# MA_board_2.net
KiCad netlist of a schematic drawn in EAGLE
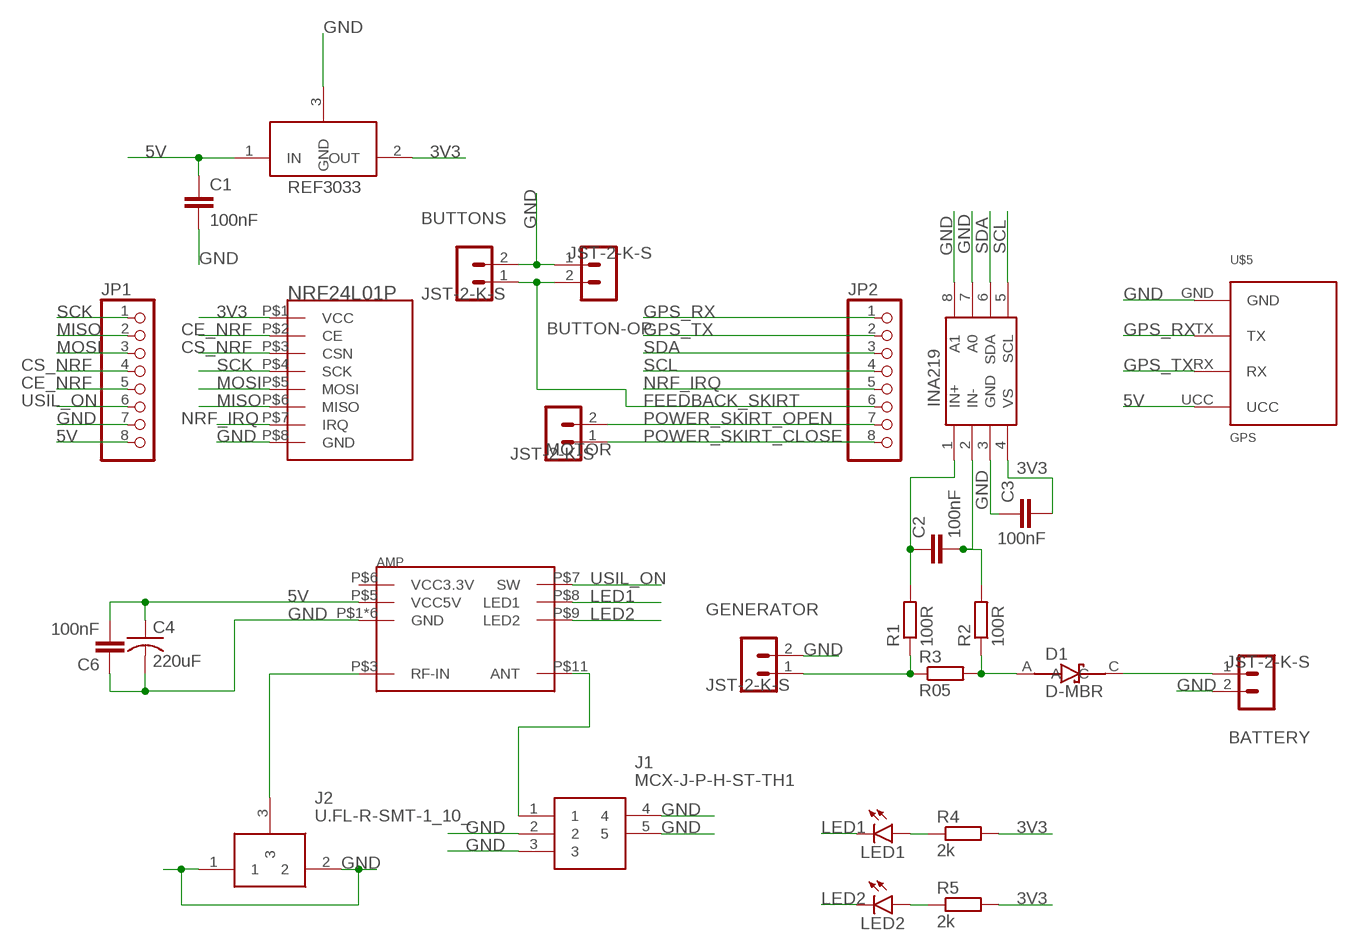
[diagram p0: schematic, sheet 1]

(export (version "E")
  (design (tool "Eeschema 10.0.6"))
  (components
    (comp (ref "AMP")
      (value "XQ-02A")
      (footprint "eagle-import:XQ-02A")
      (libsource (lib "eagle-import") (part "XQ-02A"))
    )
    (comp (ref "BATTERY")
      (value "JST-2-K-S")
      (footprint "eagle-import:B2B-PH-K-S")
      (libsource (lib "eagle-import") (part "JST-2-K-S"))
    )
    (comp (ref "BUTTON-OP")
      (value "JST-2-K-S")
      (footprint "eagle-import:B2B-PH-K-S")
      (libsource (lib "eagle-import") (part "JST-2-K-S"))
    )
    (comp (ref "BUTTONS")
      (value "JST-2-K-S")
      (footprint "eagle-import:B2B-PH-K-S")
      (libsource (lib "eagle-import") (part "JST-2-K-S"))
    )
    (comp (ref "C1")
      (value "100nF")
      (footprint "eagle-import:C0603")
      (libsource (lib "eagle-import") (part "C-EUC0603"))
    )
    (comp (ref "C2")
      (value "100nF")
      (footprint "eagle-import:C0603")
      (libsource (lib "eagle-import") (part "C-EUC0603"))
    )
    (comp (ref "C3")
      (value "100nF")
      (footprint "eagle-import:C0603")
      (libsource (lib "eagle-import") (part "C-EUC0603"))
    )
    (comp (ref "C4")
      (value "220uF")
      (footprint "eagle-import:ECAP220-CMD")
      (libsource (lib "eagle-import") (part "ECAPECAP220"))
    )
    (comp (ref "C6")
      (value "100nF")
      (footprint "eagle-import:C0603")
      (libsource (lib "eagle-import") (part "C-EUC0603"))
    )
    (comp (ref "D1")
      (value "D-MBR")
      (footprint "eagle-import:SOD123")
      (fields (field (name "MF") "ON Semiconductor") (field (name "MP") "MBR0520LT1G"))
      (libsource (lib "eagle-import") (part "DIODE-MBR"))
    )
    (comp (ref "GENERATOR")
      (value "JST-2-K-S")
      (footprint "eagle-import:B2B-PH-K-S")
      (libsource (lib "eagle-import") (part "JST-2-K-S"))
    )
    (comp (ref "INA219")
      (value "INA219AID")
      (footprint "eagle-import:SOT23-8")
      (libsource (lib "eagle-import") (part "INA219AID"))
    )
    (comp (ref "J1")
      (value "MCX-J-P-H-ST-TH1")
      (footprint "eagle-import:MCXJPHSTTH1")
      (fields (field (name "MOUSER_PART_NUMBER") "200-MCXJPHSTTH1"))
      (libsource (lib "eagle-import") (part "MCX-J-P-H-ST-TH1"))
    )
    (comp (ref "J2")
      (value "U.FL-R-SMT-1_10_")
      (footprint "eagle-import:U.FL-R-SMT-1(10)")
      (fields
        (field (name "ARROW_PART_NUMBER") "U.FL-R-SMT-1(10)")
        (field (name "MOUSER_PART_NUMBER") "798-U.FL-R-SMT-110")
      )
      (libsource (lib "eagle-import") (part "U.FL-R-SMT-1_10_"))
    )
    (comp (ref "JP1")
      (value "PINHD-1X8-SHORT-PAD")
      (footprint "eagle-import:1X08")
      (libsource (lib "eagle-import") (part "PINHD-1X8-SHORT-PAD"))
    )
    (comp (ref "JP2")
      (value "PINHD-1X8-SHORT-PAD")
      (footprint "eagle-import:1X08")
      (libsource (lib "eagle-import") (part "PINHD-1X8-SHORT-PAD"))
    )
    (comp (ref "LED1")
      (value "LEDSML0603")
      (footprint "eagle-import:SML0603")
      (libsource (lib "eagle-import") (part "LEDSML0603"))
    )
    (comp (ref "LED2")
      (value "LEDSML0603")
      (footprint "eagle-import:SML0603")
      (libsource (lib "eagle-import") (part "LEDSML0603"))
    )
    (comp (ref "MOTOR")
      (value "JST-2-K-S")
      (footprint "eagle-import:B2B-PH-K-S")
      (libsource (lib "eagle-import") (part "JST-2-K-S"))
    )
    (comp (ref "NRF24L01P")
      (value "NRF24L01_ML01SP4")
      (footprint "eagle-import:NRF24L01_ML01SP4")
      (libsource (lib "eagle-import") (part "NRF24L01_ML01SP4"))
    )
    (comp (ref "R1")
      (value "100R")
      (footprint "eagle-import:R0603")
      (libsource (lib "eagle-import") (part "R-EU_R0603"))
    )
    (comp (ref "R2")
      (value "100R")
      (footprint "eagle-import:R0603")
      (libsource (lib "eagle-import") (part "R-EU_R0603"))
    )
    (comp (ref "R3")
      (value "R05")
      (footprint "eagle-import:R2512")
      (libsource (lib "eagle-import") (part "R-EU_R2512"))
    )
    (comp (ref "R4")
      (value "2k")
      (footprint "eagle-import:R0603")
      (libsource (lib "eagle-import") (part "R-EU_R0603"))
    )
    (comp (ref "R5")
      (value "2k")
      (footprint "eagle-import:R0603")
      (libsource (lib "eagle-import") (part "R-EU_R0603"))
    )
    (comp (ref "REF3033")
      (value "REF3033")
      (footprint "eagle-import:SOT23-3")
      (libsource (lib "eagle-import") (part "REF3033"))
    )
    (comp (ref "U$5")
      (value "GPS")
      (footprint "eagle-import:GPS")
      (libsource (lib "eagle-import") (part "GPS"))
    )
  )
  (nets
    (net (code "1") (name "/3V3") (class "Default")
      (node (ref "C3") (pin "2") (pinfunction "2_2") (pintype "passive"))
      (node (ref "INA219") (pin "4") (pinfunction "VS_4") (pintype "bidirectional"))
      (node (ref "NRF24L01P") (pin "P$1") (pinfunction "VCC_P$1") (pintype "bidirectional"))
      (node (ref "R4") (pin "2") (pinfunction "2_2") (pintype "passive"))
      (node (ref "R5") (pin "2") (pinfunction "2_2") (pintype "passive"))
      (node (ref "REF3033") (pin "2") (pinfunction "OUT_2") (pintype "output"))
    )
    (net (code "2") (name "/5V") (class "Default")
      (node (ref "AMP") (pin "P$5") (pinfunction "VCC5V_P$5") (pintype "bidirectional"))
      (node (ref "C1") (pin "1") (pinfunction "1_1") (pintype "passive"))
      (node (ref "C4") (pin "P$1") (pinfunction "1_P$1") (pintype "passive"))
      (node (ref "C6") (pin "2") (pinfunction "2_2") (pintype "passive"))
      (node (ref "JP1") (pin "8") (pinfunction "8_8") (pintype "passive"))
      (node (ref "REF3033") (pin "1") (pinfunction "IN_1") (pintype "input"))
      (node (ref "U$5") (pin "UCC") (pinfunction "UCC_UCC") (pintype "bidirectional"))
    )
    (net (code "3") (name "/CE_NRF") (class "Default")
      (node (ref "JP1") (pin "5") (pinfunction "5_5") (pintype "passive"))
      (node (ref "NRF24L01P") (pin "P$2") (pinfunction "CE_P$2") (pintype "bidirectional"))
    )
    (net (code "4") (name "/CS_NRF") (class "Default")
      (node (ref "JP1") (pin "4") (pinfunction "4_4") (pintype "passive"))
      (node (ref "NRF24L01P") (pin "P$3") (pinfunction "CSN_P$3") (pintype "bidirectional"))
    )
    (net (code "5") (name "/FEEDBACK_SKIRT") (class "Default")
      (node (ref "BUTTON-OP") (pin "2") (pinfunction "2_2") (pintype "passive"))
      (node (ref "BUTTONS") (pin "1") (pinfunction "1_1") (pintype "passive"))
      (node (ref "JP2") (pin "6") (pinfunction "6_6") (pintype "passive"))
    )
    (net (code "6") (name "/GND") (class "Default")
      (node (ref "AMP") (pin "P$1") (pinfunction "GND_P$1") (pintype "bidirectional"))
      (node (ref "AMP") (pin "P$10") (pinfunction "GND_P$10") (pintype "bidirectional"))
      (node (ref "AMP") (pin "P$12") (pinfunction "GND_P$12") (pintype "bidirectional"))
      (node (ref "AMP") (pin "P$13") (pinfunction "GND_P$13") (pintype "bidirectional"))
      (node (ref "AMP") (pin "P$2") (pinfunction "GND_P$2") (pintype "bidirectional"))
      (node (ref "AMP") (pin "P$4") (pinfunction "GND_P$4") (pintype "bidirectional"))
      (node (ref "BATTERY") (pin "2") (pinfunction "2_2") (pintype "passive"))
      (node (ref "BUTTON-OP") (pin "1") (pinfunction "1_1") (pintype "passive"))
      (node (ref "BUTTONS") (pin "2") (pinfunction "2_2") (pintype "passive"))
      (node (ref "C1") (pin "2") (pinfunction "2_2") (pintype "passive"))
      (node (ref "C3") (pin "1") (pinfunction "1_1") (pintype "passive"))
      (node (ref "C4") (pin "P$2") (pinfunction "2_P$2") (pintype "passive"))
      (node (ref "C6") (pin "1") (pinfunction "1_1") (pintype "passive"))
      (node (ref "GENERATOR") (pin "2") (pinfunction "2_2") (pintype "passive"))
      (node (ref "INA219") (pin "3") (pinfunction "GND_3") (pintype "bidirectional"))
      (node (ref "INA219") (pin "7") (pinfunction "A0_7") (pintype "bidirectional"))
      (node (ref "INA219") (pin "8") (pinfunction "A1_8") (pintype "bidirectional"))
      (node (ref "J1") (pin "2") (pinfunction "2_2") (pintype "bidirectional"))
      (node (ref "J1") (pin "3") (pinfunction "3_3") (pintype "bidirectional"))
      (node (ref "J1") (pin "4") (pinfunction "4_4") (pintype "bidirectional"))
      (node (ref "J1") (pin "5") (pinfunction "5_5") (pintype "bidirectional"))
      (node (ref "J2") (pin "1") (pinfunction "1_1") (pintype "bidirectional"))
      (node (ref "J2") (pin "2") (pinfunction "2_2") (pintype "bidirectional"))
      (node (ref "JP1") (pin "7") (pinfunction "7_7") (pintype "passive"))
      (node (ref "NRF24L01P") (pin "P$8") (pinfunction "GND_P$8") (pintype "bidirectional"))
      (node (ref "REF3033") (pin "3") (pinfunction "GND_3") (pintype "power_in"))
      (node (ref "U$5") (pin "GND") (pinfunction "GND_GND") (pintype "bidirectional"))
    )
    (net (code "7") (name "/GPS_RX") (class "Default")
      (node (ref "JP2") (pin "1") (pinfunction "1_1") (pintype "passive"))
      (node (ref "U$5") (pin "TX") (pinfunction "TX_TX") (pintype "bidirectional"))
    )
    (net (code "8") (name "/GPS_TX") (class "Default")
      (node (ref "JP2") (pin "2") (pinfunction "2_2") (pintype "passive"))
      (node (ref "U$5") (pin "RX") (pinfunction "RX_RX") (pintype "bidirectional"))
    )
    (net (code "9") (name "/LED1") (class "Default")
      (node (ref "AMP") (pin "P$8") (pinfunction "LED1_P$8") (pintype "bidirectional"))
      (node (ref "LED1") (pin "C") (pinfunction "C_C") (pintype "passive"))
    )
    (net (code "10") (name "/LED2") (class "Default")
      (node (ref "AMP") (pin "P$9") (pinfunction "LED2_P$9") (pintype "bidirectional"))
      (node (ref "LED2") (pin "C") (pinfunction "C_C") (pintype "passive"))
    )
    (net (code "11") (name "/MISO") (class "Default")
      (node (ref "JP1") (pin "2") (pinfunction "2_2") (pintype "passive"))
      (node (ref "NRF24L01P") (pin "P$6") (pinfunction "MISO_P$6") (pintype "bidirectional"))
    )
    (net (code "12") (name "/MOSI") (class "Default")
      (node (ref "JP1") (pin "3") (pinfunction "3_3") (pintype "passive"))
      (node (ref "NRF24L01P") (pin "P$5") (pinfunction "MOSI_P$5") (pintype "bidirectional"))
    )
    (net (code "13") (name "/NRF_IRQ") (class "Default")
      (node (ref "JP2") (pin "5") (pinfunction "5_5") (pintype "passive"))
      (node (ref "NRF24L01P") (pin "P$7") (pinfunction "IRQ_P$7") (pintype "bidirectional"))
    )
    (net (code "14") (name "/POWER_SKIRT_CLOSE") (class "Default")
      (node (ref "JP2") (pin "8") (pinfunction "8_8") (pintype "passive"))
      (node (ref "MOTOR") (pin "1") (pinfunction "1_1") (pintype "passive"))
    )
    (net (code "15") (name "/POWER_SKIRT_OPEN") (class "Default")
      (node (ref "JP2") (pin "7") (pinfunction "7_7") (pintype "passive"))
      (node (ref "MOTOR") (pin "2") (pinfunction "2_2") (pintype "passive"))
    )
    (net (code "16") (name "/SCK") (class "Default")
      (node (ref "JP1") (pin "1") (pinfunction "1_1") (pintype "passive"))
      (node (ref "NRF24L01P") (pin "P$4") (pinfunction "SCK_P$4") (pintype "bidirectional"))
    )
    (net (code "17") (name "/SCL") (class "Default")
      (node (ref "INA219") (pin "5") (pinfunction "SCL_5") (pintype "bidirectional"))
      (node (ref "JP2") (pin "4") (pinfunction "4_4") (pintype "passive"))
    )
    (net (code "18") (name "/SDA") (class "Default")
      (node (ref "INA219") (pin "6") (pinfunction "SDA_6") (pintype "bidirectional"))
      (node (ref "JP2") (pin "3") (pinfunction "3_3") (pintype "passive"))
    )
    (net (code "19") (name "/USIL_ON") (class "Default")
      (node (ref "AMP") (pin "P$7") (pinfunction "SW_P$7") (pintype "bidirectional"))
      (node (ref "JP1") (pin "6") (pinfunction "6_6") (pintype "passive"))
    )
    (net (code "20") (name "Net-(AMP-ANT)") (class "Default")
      (node (ref "AMP") (pin "P$11") (pinfunction "ANT_P$11") (pintype "bidirectional"))
      (node (ref "J1") (pin "1") (pinfunction "1_1") (pintype "bidirectional"))
    )
    (net (code "21") (name "Net-(AMP-RF-IN)") (class "Default")
      (node (ref "AMP") (pin "P$3") (pinfunction "RF-IN_P$3") (pintype "bidirectional"))
      (node (ref "J2") (pin "3") (pinfunction "3_3") (pintype "bidirectional"))
    )
    (net (code "22") (name "Net-(BATTERY-Pad1)") (class "Default")
      (node (ref "BATTERY") (pin "1") (pinfunction "1_1") (pintype "passive"))
      (node (ref "D1") (pin "C") (pinfunction "C_C") (pintype "passive"))
    )
    (net (code "23") (name "Net-(D1-PadA)") (class "Default")
      (node (ref "D1") (pin "A") (pinfunction "A_A") (pintype "passive"))
      (node (ref "R2") (pin "1") (pinfunction "1_1") (pintype "passive"))
      (node (ref "R3") (pin "2") (pinfunction "2_2") (pintype "passive"))
    )
    (net (code "24") (name "Net-(GENERATOR-Pad1)") (class "Default")
      (node (ref "GENERATOR") (pin "1") (pinfunction "1_1") (pintype "passive"))
      (node (ref "R1") (pin "1") (pinfunction "1_1") (pintype "passive"))
      (node (ref "R3") (pin "1") (pinfunction "1_1") (pintype "passive"))
    )
    (net (code "25") (name "Net-(INA219-IN+)") (class "Default")
      (node (ref "C2") (pin "1") (pinfunction "1_1") (pintype "passive"))
      (node (ref "INA219") (pin "1") (pinfunction "IN+_1") (pintype "bidirectional"))
      (node (ref "R1") (pin "2") (pinfunction "2_2") (pintype "passive"))
    )
    (net (code "26") (name "Net-(INA219-IN-)") (class "Default")
      (node (ref "C2") (pin "2") (pinfunction "2_2") (pintype "passive"))
      (node (ref "INA219") (pin "2") (pinfunction "IN-_2") (pintype "bidirectional"))
      (node (ref "R2") (pin "2") (pinfunction "2_2") (pintype "passive"))
    )
    (net (code "27") (name "Net-(LED1-PadA)") (class "Default")
      (node (ref "LED1") (pin "A") (pinfunction "A_A") (pintype "passive"))
      (node (ref "R4") (pin "1") (pinfunction "1_1") (pintype "passive"))
    )
    (net (code "28") (name "Net-(LED2-PadA)") (class "Default")
      (node (ref "LED2") (pin "A") (pinfunction "A_A") (pintype "passive"))
      (node (ref "R5") (pin "1") (pinfunction "1_1") (pintype "passive"))
    )
    (net (code "29") (name "unconnected-(AMP-VCC3.3V-PadP$6)") (class "Default")
      (node (ref "AMP") (pin "P$6") (pinfunction "VCC3.3V_P$6") (pintype "bidirectional"))
    )
  )
)
